# -AltiumDesigner.net
KiCad netlist of a schematic drawn in Altium Designer
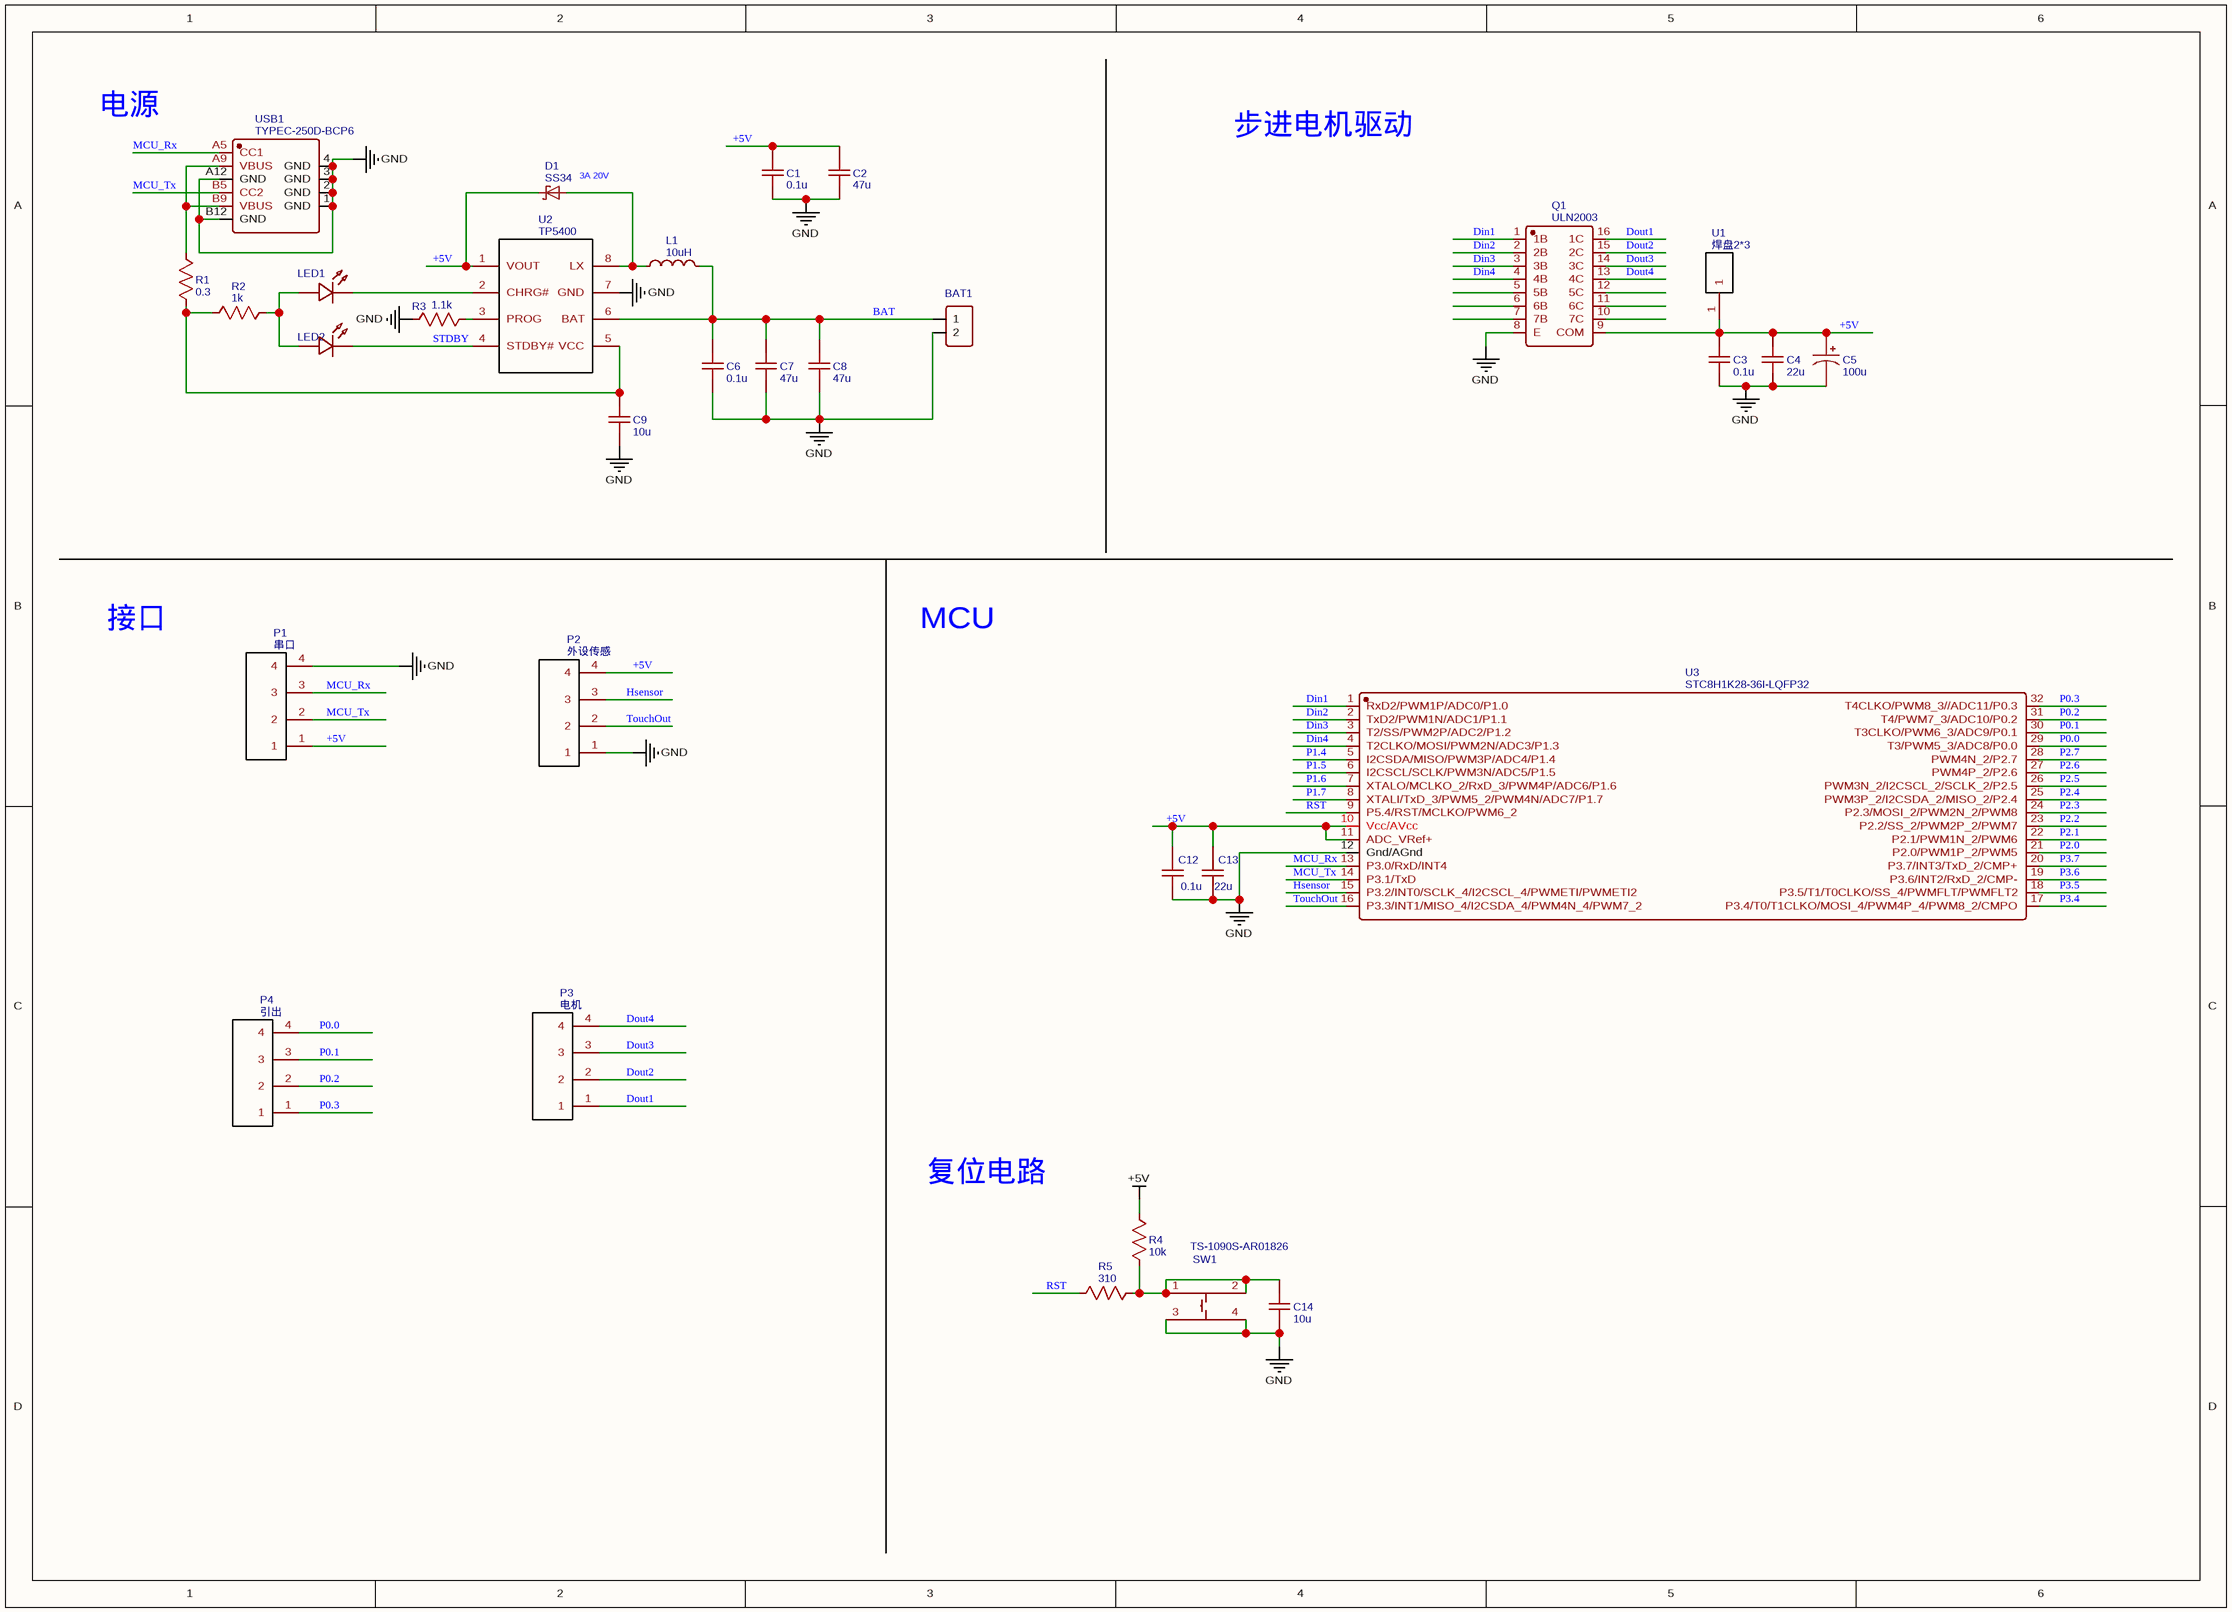
[diagram p0: 人体感应灯控-AltiumDesigner.schdoc]

(export (version "E")
  (design (tool "Eeschema 10.0.6"))
  (components
    (comp (ref "BAT1")
      (value "HDR-F-2.54_1x2")
      (fields (field (name "BOM_SUPPLIER PART") "C49661") (field (name "CONTRIBUTOR") "LCEDA_Lib"))
      (libsource (lib "altium-import") (part "root_0_HDR-F-2.54_1x2_"))
    )
    (comp (ref "C1")
      (value "0.1u")
      (fields (field (name "CONTRIBUTOR") "LCEDA_Lib"))
      (libsource (lib "altium-import") (part "root_1_0.1u_"))
    )
    (comp (ref "C2")
      (value "47u")
      (fields (field (name "CONTRIBUTOR") "LCEDA_Lib"))
      (libsource (lib "altium-import") (part "root_1_47u_"))
    )
    (comp (ref "C3")
      (value "0.1u")
      (fields (field (name "CONTRIBUTOR") "LCEDA_Lib"))
      (libsource (lib "altium-import") (part "root_1_0.1u_"))
    )
    (comp (ref "C4")
      (value "22u")
      (fields (field (name "CONTRIBUTOR") "LCEDA_Lib"))
      (libsource (lib "altium-import") (part "root_1_22u_"))
    )
    (comp (ref "C5")
      (value "100u")
      (fields (field (name "CONTRIBUTOR") "LCEDA_Lib"))
      (libsource (lib "altium-import") (part "root_3_100u_"))
    )
    (comp (ref "C6")
      (value "0.1u")
      (fields (field (name "CONTRIBUTOR") "LCEDA_Lib"))
      (libsource (lib "altium-import") (part "root_1_0.1u_"))
    )
    (comp (ref "C7")
      (value "47u")
      (fields (field (name "CONTRIBUTOR") "LCEDA_Lib"))
      (libsource (lib "altium-import") (part "root_1_47u_"))
    )
    (comp (ref "C8")
      (value "47u")
      (fields (field (name "CONTRIBUTOR") "LCEDA_Lib"))
      (libsource (lib "altium-import") (part "root_1_47u_"))
    )
    (comp (ref "C9")
      (value "10u")
      (fields (field (name "CONTRIBUTOR") "LCEDA_Lib"))
      (libsource (lib "altium-import") (part "root_1_10u_"))
    )
    (comp (ref "C12")
      (value "0.1u")
      (fields (field (name "CONTRIBUTOR") "LCEDA_Lib"))
      (libsource (lib "altium-import") (part "root_1_0.1u_"))
    )
    (comp (ref "C13")
      (value "22u")
      (fields (field (name "CONTRIBUTOR") "LCEDA_Lib"))
      (libsource (lib "altium-import") (part "root_1_22u_"))
    )
    (comp (ref "C14")
      (value "10u")
      (fields (field (name "CONTRIBUTOR") "LCEDA_Lib"))
      (libsource (lib "altium-import") (part "root_1_10u_"))
    )
    (comp (ref "D1") (value "SS34") (libsource (lib "altium-import") (part "root_2_SS34_")))
    (comp (ref "L1")
      (value "10uH")
      (fields (field (name "CONTRIBUTOR") "LCEDA_Lib"))
      (libsource (lib "altium-import") (part "root_0_10uH_"))
    )
    (comp (ref "LED1")
      (value "LED-0603_R")
      (fields
        (field (name "BOM_MANUFACTURER PART") "19-217/R6C-AL1M2VY/3T")
        (field (name "BOM_SUPPLIER PART") "C72044")
        (field (name "CONTRIBUTOR") "LCEDA_01")
      )
      (libsource (lib "altium-import") (part "root_0_LED-0603_R_"))
    )
    (comp (ref "LED2")
      (value "LED-0603_R")
      (fields
        (field (name "BOM_MANUFACTURER PART") "19-217/R6C-AL1M2VY/3T")
        (field (name "BOM_SUPPLIER PART") "C72044")
        (field (name "CONTRIBUTOR") "LCEDA_01")
      )
      (libsource (lib "altium-import") (part "root_0_LED-0603_R_"))
    )
    (comp (ref "P1")
      (value "串口")
      (fields
        (field (name "BOM_MANUFACTURER PART") "New SchematicLib")
        (field (name "CONTRIBUTOR") "zhouweitian8888")
      )
      (libsource (lib "altium-import") (part "root_2_串口_"))
    )
    (comp (ref "P2")
      (value "外设传感")
      (fields
        (field (name "BOM_MANUFACTURER PART") "New SchematicLib")
        (field (name "CONTRIBUTOR") "zhouweitian8888")
      )
      (libsource (lib "altium-import") (part "root_2_外设传感_"))
    )
    (comp (ref "P3")
      (value "电机")
      (fields
        (field (name "BOM_MANUFACTURER PART") "New SchematicLib")
        (field (name "CONTRIBUTOR") "zhouweitian8888")
      )
      (libsource (lib "altium-import") (part "root_2_电机_"))
    )
    (comp (ref "P4")
      (value "引出")
      (fields
        (field (name "BOM_MANUFACTURER PART") "New SchematicLib")
        (field (name "CONTRIBUTOR") "zhouweitian8888")
      )
      (libsource (lib "altium-import") (part "root_2_引出_"))
    )
    (comp (ref "Q1")
      (value "ULN2003")
      (fields (field (name "BOM_SUPPLIER PART") "C411052") (field (name "CONTRIBUTOR") "LCSC"))
      (libsource (lib "altium-import") (part "root_0_ULN2003_"))
    )
    (comp (ref "R1")
      (value "0.3")
      (fields (field (name "CONTRIBUTOR") "LCEDA_Lib"))
      (libsource (lib "altium-import") (part "root_3_0.3_"))
    )
    (comp (ref "R2")
      (value "1k")
      (fields (field (name "CONTRIBUTOR") "LCEDA_Lib"))
      (libsource (lib "altium-import") (part "root_2_1k_"))
    )
    (comp (ref "R3")
      (value "1.1k")
      (fields (field (name "CONTRIBUTOR") "LCEDA_Lib"))
      (libsource (lib "altium-import") (part "root_2_1.1k_"))
    )
    (comp (ref "R4")
      (value "10k")
      (fields (field (name "CONTRIBUTOR") "LCEDA_Lib"))
      (libsource (lib "altium-import") (part "root_1_10k_"))
    )
    (comp (ref "R5")
      (value "310")
      (fields (field (name "CONTRIBUTOR") "LCEDA_Lib"))
      (libsource (lib "altium-import") (part "root_2_310_"))
    )
    (comp (ref "SW1")
      (value "TS-1090S-AR01826")
      (fields (field (name "BOM_SUPPLIER PART") "C920224") (field (name "CONTRIBUTOR") "LCSC"))
      (libsource (lib "altium-import") (part "root_0_TS-1090S-AR01826_"))
    )
    (comp (ref "U1")
      (value "焊盘2*3")
      (fields (field (name "CONTRIBUTOR") "Tsinghua_Lee"))
      (libsource (lib "altium-import") (part "root_1_焊盘2*3_"))
    )
    (comp (ref "U2")
      (value "TP5400")
      (fields (field (name "BOM_SUPPLIER PART") "C24154"))
      (libsource (lib "altium-import") (part "root_0_TP5400_"))
    )
    (comp (ref "U3")
      (value "STC8H1K28-36I-LQFP32")
      (fields (field (name "BOM_SUPPLIER PART") "C914618") (field (name "CONTRIBUTOR") "LCSC"))
      (libsource (lib "altium-import") (part "root_0_STC8H1K28-36I-LQFP32_"))
    )
    (comp (ref "USB1")
      (value "TYPEC-250D-BCP6")
      (fields (field (name "BOM_SUPPLIER PART") "C720626") (field (name "CONTRIBUTOR") "LCSC"))
      (libsource (lib "altium-import") (part "root_0_TYPEC-250D-BCP6_"))
    )
  )
  (nets
    (net (code "1") (name "+5V") (class "Default")
      (node (ref "C1") (pin "2") (pinfunction "2_2") (pintype "passive"))
      (node (ref "C12") (pin "2") (pinfunction "2_2") (pintype "passive"))
      (node (ref "C13") (pin "2") (pinfunction "2_2") (pintype "passive"))
      (node (ref "C2") (pin "2") (pinfunction "2_2") (pintype "passive"))
      (node (ref "C3") (pin "2") (pinfunction "2_2") (pintype "passive"))
      (node (ref "C4") (pin "2") (pinfunction "2_2") (pintype "passive"))
      (node (ref "C5") (pin "1") (pinfunction "1_1") (pintype "passive"))
      (node (ref "D1") (pin "C") (pinfunction "C_C") (pintype "passive"))
      (node (ref "P1") (pin "1") (pinfunction "1_1") (pintype "passive"))
      (node (ref "P2") (pin "4") (pinfunction "4_4") (pintype "passive"))
      (node (ref "Q1") (pin "9") (pinfunction "COM_9") (pintype "passive"))
      (node (ref "R4") (pin "2") (pinfunction "2_2") (pintype "passive"))
      (node (ref "U1") (pin "1") (pinfunction "1_1") (pintype "passive"))
      (node (ref "U2") (pin "1") (pinfunction "VOUT_1") (pintype "passive"))
      (node (ref "U3") (pin "10") (pinfunction "Vcc/AVcc_10") (pintype "passive"))
      (node (ref "U3") (pin "11") (pinfunction "ADC_VRef+_11") (pintype "passive"))
    )
    (net (code "2") (name "/BAT") (class "Default")
      (node (ref "BAT1") (pin "1") (pinfunction "1_1") (pintype "passive"))
      (node (ref "C6") (pin "2") (pinfunction "2_2") (pintype "passive"))
      (node (ref "C7") (pin "2") (pinfunction "2_2") (pintype "passive"))
      (node (ref "C8") (pin "2") (pinfunction "2_2") (pintype "passive"))
      (node (ref "L1") (pin "2") (pinfunction "2_2") (pintype "passive"))
      (node (ref "U2") (pin "6") (pinfunction "BAT_6") (pintype "passive"))
    )
    (net (code "3") (name "/Din1") (class "Default")
      (node (ref "Q1") (pin "1") (pinfunction "1B_1") (pintype "passive"))
      (node (ref "U3") (pin "1") (pinfunction "RxD2/PWM1P/ADC0/P1.0_1") (pintype "passive"))
    )
    (net (code "4") (name "/Din2") (class "Default")
      (node (ref "Q1") (pin "2") (pinfunction "2B_2") (pintype "passive"))
      (node (ref "U3") (pin "2") (pinfunction "TxD2/PWM1N/ADC1/P1.1_2") (pintype "passive"))
    )
    (net (code "5") (name "/Din3") (class "Default")
      (node (ref "Q1") (pin "3") (pinfunction "3B_3") (pintype "passive"))
      (node (ref "U3") (pin "3") (pinfunction "T2/SS/PWM2P/ADC2/P1.2_3") (pintype "passive"))
    )
    (net (code "6") (name "/Din4") (class "Default")
      (node (ref "Q1") (pin "4") (pinfunction "4B_4") (pintype "passive"))
      (node (ref "U3") (pin "4") (pinfunction "T2CLKO/MOSI/PWM2N/ADC3/P1.3_4") (pintype "passive"))
    )
    (net (code "7") (name "/Dout1") (class "Default")
      (node (ref "P3") (pin "1") (pinfunction "1_1") (pintype "passive"))
      (node (ref "Q1") (pin "16") (pinfunction "1C_16") (pintype "passive"))
    )
    (net (code "8") (name "/Dout2") (class "Default")
      (node (ref "P3") (pin "2") (pinfunction "2_2") (pintype "passive"))
      (node (ref "Q1") (pin "15") (pinfunction "2C_15") (pintype "passive"))
    )
    (net (code "9") (name "/Dout3") (class "Default")
      (node (ref "P3") (pin "3") (pinfunction "3_3") (pintype "passive"))
      (node (ref "Q1") (pin "14") (pinfunction "3C_14") (pintype "passive"))
    )
    (net (code "10") (name "/Dout4") (class "Default")
      (node (ref "P3") (pin "4") (pinfunction "4_4") (pintype "passive"))
      (node (ref "Q1") (pin "13") (pinfunction "4C_13") (pintype "passive"))
    )
    (net (code "11") (name "/Hsensor") (class "Default")
      (node (ref "P2") (pin "3") (pinfunction "3_3") (pintype "passive"))
      (node (ref "U3") (pin "15") (pinfunction "P3.2/INT0/SCLK_4/I2CSCL_4/PWMETI/PWMETI2_15") (pintype "passive"))
    )
    (net (code "12") (name "/MCU_Rx") (class "Default")
      (node (ref "P1") (pin "3") (pinfunction "3_3") (pintype "passive"))
      (node (ref "U3") (pin "13") (pinfunction "P3.0/RxD/INT4_13") (pintype "passive"))
      (node (ref "USB1") (pin "A5") (pinfunction "CC1_A5") (pintype "passive"))
    )
    (net (code "13") (name "/MCU_Tx") (class "Default")
      (node (ref "P1") (pin "2") (pinfunction "2_2") (pintype "passive"))
      (node (ref "U3") (pin "14") (pinfunction "P3.1/TxD_14") (pintype "passive"))
      (node (ref "USB1") (pin "B5") (pinfunction "CC2_B5") (pintype "passive"))
    )
    (net (code "14") (name "/P0.0") (class "Default")
      (node (ref "P4") (pin "4") (pinfunction "4_4") (pintype "passive"))
      (node (ref "U3") (pin "29") (pinfunction "T3/PWM5_3/ADC8/P0.0_29") (pintype "passive"))
    )
    (net (code "15") (name "/P0.1") (class "Default")
      (node (ref "P4") (pin "3") (pinfunction "3_3") (pintype "passive"))
      (node (ref "U3") (pin "30") (pinfunction "T3CLKO/PWM6_3/ADC9/P0.1_30") (pintype "passive"))
    )
    (net (code "16") (name "/P0.2") (class "Default")
      (node (ref "P4") (pin "2") (pinfunction "2_2") (pintype "passive"))
      (node (ref "U3") (pin "31") (pinfunction "T4/PWM7_3/ADC10/P0.2_31") (pintype "passive"))
    )
    (net (code "17") (name "/P0.3") (class "Default")
      (node (ref "P4") (pin "1") (pinfunction "1_1") (pintype "passive"))
      (node (ref "U3") (pin "32") (pinfunction "T4CLKO/PWM8_3//ADC11/P0.3_32") (pintype "passive"))
    )
    (net (code "18") (name "/P1.4") (class "Default")
      (node (ref "U3") (pin "5") (pinfunction "I2CSDA/MISO/PWM3P/ADC4/P1.4_5") (pintype "passive"))
    )
    (net (code "19") (name "/P1.5") (class "Default")
      (node (ref "U3") (pin "6") (pinfunction "I2CSCL/SCLK/PWM3N/ADC5/P1.5_6") (pintype "passive"))
    )
    (net (code "20") (name "/P1.6") (class "Default")
      (node (ref "U3") (pin "7") (pinfunction "XTALO/MCLKO_2/RxD_3/PWM4P/ADC6/P1.6_7") (pintype "passive"))
    )
    (net (code "21") (name "/P1.7") (class "Default")
      (node (ref "U3") (pin "8") (pinfunction "XTALI/TxD_3/PWM5_2/PWM4N/ADC7/P1.7_8") (pintype "passive"))
    )
    (net (code "22") (name "/P2.0") (class "Default")
      (node (ref "U3") (pin "21") (pinfunction "P2.0/PWM1P_2/PWM5_21") (pintype "passive"))
    )
    (net (code "23") (name "/P2.1") (class "Default")
      (node (ref "U3") (pin "22") (pinfunction "P2.1/PWM1N_2/PWM6_22") (pintype "passive"))
    )
    (net (code "24") (name "/P2.2") (class "Default")
      (node (ref "U3") (pin "23") (pinfunction "P2.2/SS_2/PWM2P_2/PWM7_23") (pintype "passive"))
    )
    (net (code "25") (name "/P2.3") (class "Default")
      (node (ref "U3") (pin "24") (pinfunction "P2.3/MOSI_2/PWM2N_2/PWM8_24") (pintype "passive"))
    )
    (net (code "26") (name "/P2.4") (class "Default")
      (node (ref "U3") (pin "25") (pinfunction "PWM3P_2/I2CSDA_2/MISO_2/P2.4_25") (pintype "passive"))
    )
    (net (code "27") (name "/P2.5") (class "Default")
      (node (ref "U3") (pin "26") (pinfunction "PWM3N_2/I2CSCL_2/SCLK_2/P2.5_26") (pintype "passive"))
    )
    (net (code "28") (name "/P2.6") (class "Default")
      (node (ref "U3") (pin "27") (pinfunction "PWM4P_2/P2.6_27") (pintype "passive"))
    )
    (net (code "29") (name "/P2.7") (class "Default")
      (node (ref "U3") (pin "28") (pinfunction "PWM4N_2/P2.7_28") (pintype "passive"))
    )
    (net (code "30") (name "/P3.4") (class "Default")
      (node (ref "U3") (pin "17") (pinfunction "P3.4/T0/T1CLKO/MOSI_4/PWM4P_4/PWM8_2/CMPO_17") (pintype "passive"))
    )
    (net (code "31") (name "/P3.5") (class "Default")
      (node (ref "U3") (pin "18") (pinfunction "P3.5/T1/T0CLKO/SS_4/PWMFLT/PWMFLT2_18") (pintype "passive"))
    )
    (net (code "32") (name "/P3.6") (class "Default")
      (node (ref "U3") (pin "19") (pinfunction "P3.6/INT2/RxD_2/CMP-_19") (pintype "passive"))
    )
    (net (code "33") (name "/P3.7") (class "Default")
      (node (ref "U3") (pin "20") (pinfunction "P3.7/INT3/TxD_2/CMP+_20") (pintype "passive"))
    )
    (net (code "34") (name "/RST") (class "Default")
      (node (ref "R5") (pin "2") (pinfunction "2_2") (pintype "passive"))
      (node (ref "U3") (pin "9") (pinfunction "P5.4/RST/MCLKO/PWM6_2_9") (pintype "passive"))
    )
    (net (code "35") (name "/STDBY") (class "Default")
      (node (ref "LED2") (pin "2") (pinfunction "2_2") (pintype "passive"))
      (node (ref "U2") (pin "4") (pinfunction "STDBY#_4") (pintype "passive"))
    )
    (net (code "36") (name "/TouchOut") (class "Default")
      (node (ref "P2") (pin "2") (pinfunction "2_2") (pintype "passive"))
      (node (ref "U3") (pin "16") (pinfunction "P3.3/INT1/MISO_4/I2CSDA_4/PWM4N_4/PWM7_2_16") (pintype "passive"))
    )
    (net (code "37") (name "GND") (class "Default")
      (node (ref "BAT1") (pin "2") (pinfunction "2_2") (pintype "passive"))
      (node (ref "C1") (pin "1") (pinfunction "1_1") (pintype "passive"))
      (node (ref "C12") (pin "1") (pinfunction "1_1") (pintype "passive"))
      (node (ref "C13") (pin "1") (pinfunction "1_1") (pintype "passive"))
      (node (ref "C14") (pin "1") (pinfunction "1_1") (pintype "passive"))
      (node (ref "C2") (pin "1") (pinfunction "1_1") (pintype "passive"))
      (node (ref "C3") (pin "1") (pinfunction "1_1") (pintype "passive"))
      (node (ref "C4") (pin "1") (pinfunction "1_1") (pintype "passive"))
      (node (ref "C5") (pin "2") (pinfunction "2_2") (pintype "passive"))
      (node (ref "C6") (pin "1") (pinfunction "1_1") (pintype "passive"))
      (node (ref "C7") (pin "1") (pinfunction "1_1") (pintype "passive"))
      (node (ref "C8") (pin "1") (pinfunction "1_1") (pintype "passive"))
      (node (ref "C9") (pin "1") (pinfunction "1_1") (pintype "passive"))
      (node (ref "P1") (pin "4") (pinfunction "4_4") (pintype "passive"))
      (node (ref "P2") (pin "1") (pinfunction "1_1") (pintype "passive"))
      (node (ref "Q1") (pin "8") (pinfunction "E_8") (pintype "passive"))
      (node (ref "R3") (pin "2") (pinfunction "2_2") (pintype "passive"))
      (node (ref "SW1") (pin "3") (pinfunction "3_3") (pintype "passive"))
      (node (ref "SW1") (pin "4") (pinfunction "4_4") (pintype "passive"))
      (node (ref "U2") (pin "7") (pinfunction "GND_7") (pintype "passive"))
      (node (ref "U3") (pin "12") (pinfunction "Gnd/AGnd_12") (pintype "passive"))
      (node (ref "USB1") (pin "1") (pinfunction "GND_1") (pintype "passive"))
      (node (ref "USB1") (pin "2") (pinfunction "GND_2") (pintype "passive"))
      (node (ref "USB1") (pin "3") (pinfunction "GND_3") (pintype "passive"))
      (node (ref "USB1") (pin "4") (pinfunction "GND_4") (pintype "passive"))
      (node (ref "USB1") (pin "A12") (pinfunction "GND_A12") (pintype "passive"))
      (node (ref "USB1") (pin "B12") (pinfunction "GND_B12") (pintype "passive"))
    )
    (net (code "38") (name "Net-(C14-Pad2)") (class "Default")
      (node (ref "C14") (pin "2") (pinfunction "2_2") (pintype "passive"))
      (node (ref "R4") (pin "1") (pinfunction "1_1") (pintype "passive"))
      (node (ref "R5") (pin "1") (pinfunction "1_1") (pintype "passive"))
      (node (ref "SW1") (pin "1") (pinfunction "1_1") (pintype "passive"))
      (node (ref "SW1") (pin "2") (pinfunction "2_2") (pintype "passive"))
    )
    (net (code "39") (name "Net-(LED1-Pad1)") (class "Default")
      (node (ref "LED1") (pin "1") (pinfunction "1_1") (pintype "passive"))
      (node (ref "LED2") (pin "1") (pinfunction "1_1") (pintype "passive"))
      (node (ref "R2") (pin "1") (pinfunction "1_1") (pintype "passive"))
    )
    (net (code "40") (name "Net-(R1-Pad1)") (class "Default")
      (node (ref "R1") (pin "1") (pinfunction "1_1") (pintype "passive"))
      (node (ref "USB1") (pin "A9") (pinfunction "VBUS_A9") (pintype "passive"))
      (node (ref "USB1") (pin "B9") (pinfunction "VBUS_B9") (pintype "passive"))
    )
    (net (code "41") (name "Net-(U2-CHRG#)") (class "Default")
      (node (ref "LED1") (pin "2") (pinfunction "2_2") (pintype "passive"))
      (node (ref "U2") (pin "2") (pinfunction "CHRG#_2") (pintype "passive"))
    )
    (net (code "42") (name "Net-(U2-LX)") (class "Default")
      (node (ref "D1") (pin "A") (pinfunction "A_A") (pintype "passive"))
      (node (ref "L1") (pin "1") (pinfunction "1_1") (pintype "passive"))
      (node (ref "U2") (pin "8") (pinfunction "LX_8") (pintype "passive"))
    )
    (net (code "43") (name "Net-(U2-PROG)") (class "Default")
      (node (ref "R3") (pin "1") (pinfunction "1_1") (pintype "passive"))
      (node (ref "U2") (pin "3") (pinfunction "PROG_3") (pintype "passive"))
    )
    (net (code "44") (name "Net-(U2-VCC)") (class "Default")
      (node (ref "C9") (pin "2") (pinfunction "2_2") (pintype "passive"))
      (node (ref "R1") (pin "2") (pinfunction "2_2") (pintype "passive"))
      (node (ref "R2") (pin "2") (pinfunction "2_2") (pintype "passive"))
      (node (ref "U2") (pin "5") (pinfunction "VCC_5") (pintype "passive"))
    )
    (net (code "45") (name "unconnected-(Q1-5B-Pad5)") (class "Default")
      (node (ref "Q1") (pin "5") (pinfunction "5B_5") (pintype "passive"))
    )
    (net (code "46") (name "unconnected-(Q1-5C-Pad12)") (class "Default")
      (node (ref "Q1") (pin "12") (pinfunction "5C_12") (pintype "passive"))
    )
    (net (code "47") (name "unconnected-(Q1-6B-Pad6)") (class "Default")
      (node (ref "Q1") (pin "6") (pinfunction "6B_6") (pintype "passive"))
    )
    (net (code "48") (name "unconnected-(Q1-6C-Pad11)") (class "Default")
      (node (ref "Q1") (pin "11") (pinfunction "6C_11") (pintype "passive"))
    )
    (net (code "49") (name "unconnected-(Q1-7B-Pad7)") (class "Default")
      (node (ref "Q1") (pin "7") (pinfunction "7B_7") (pintype "passive"))
    )
    (net (code "50") (name "unconnected-(Q1-7C-Pad10)") (class "Default")
      (node (ref "Q1") (pin "10") (pinfunction "7C_10") (pintype "passive"))
    )
  )
)
